# cpu2_lock_control1.net
KiCad netlist of a schematic drawn in Altium Designer
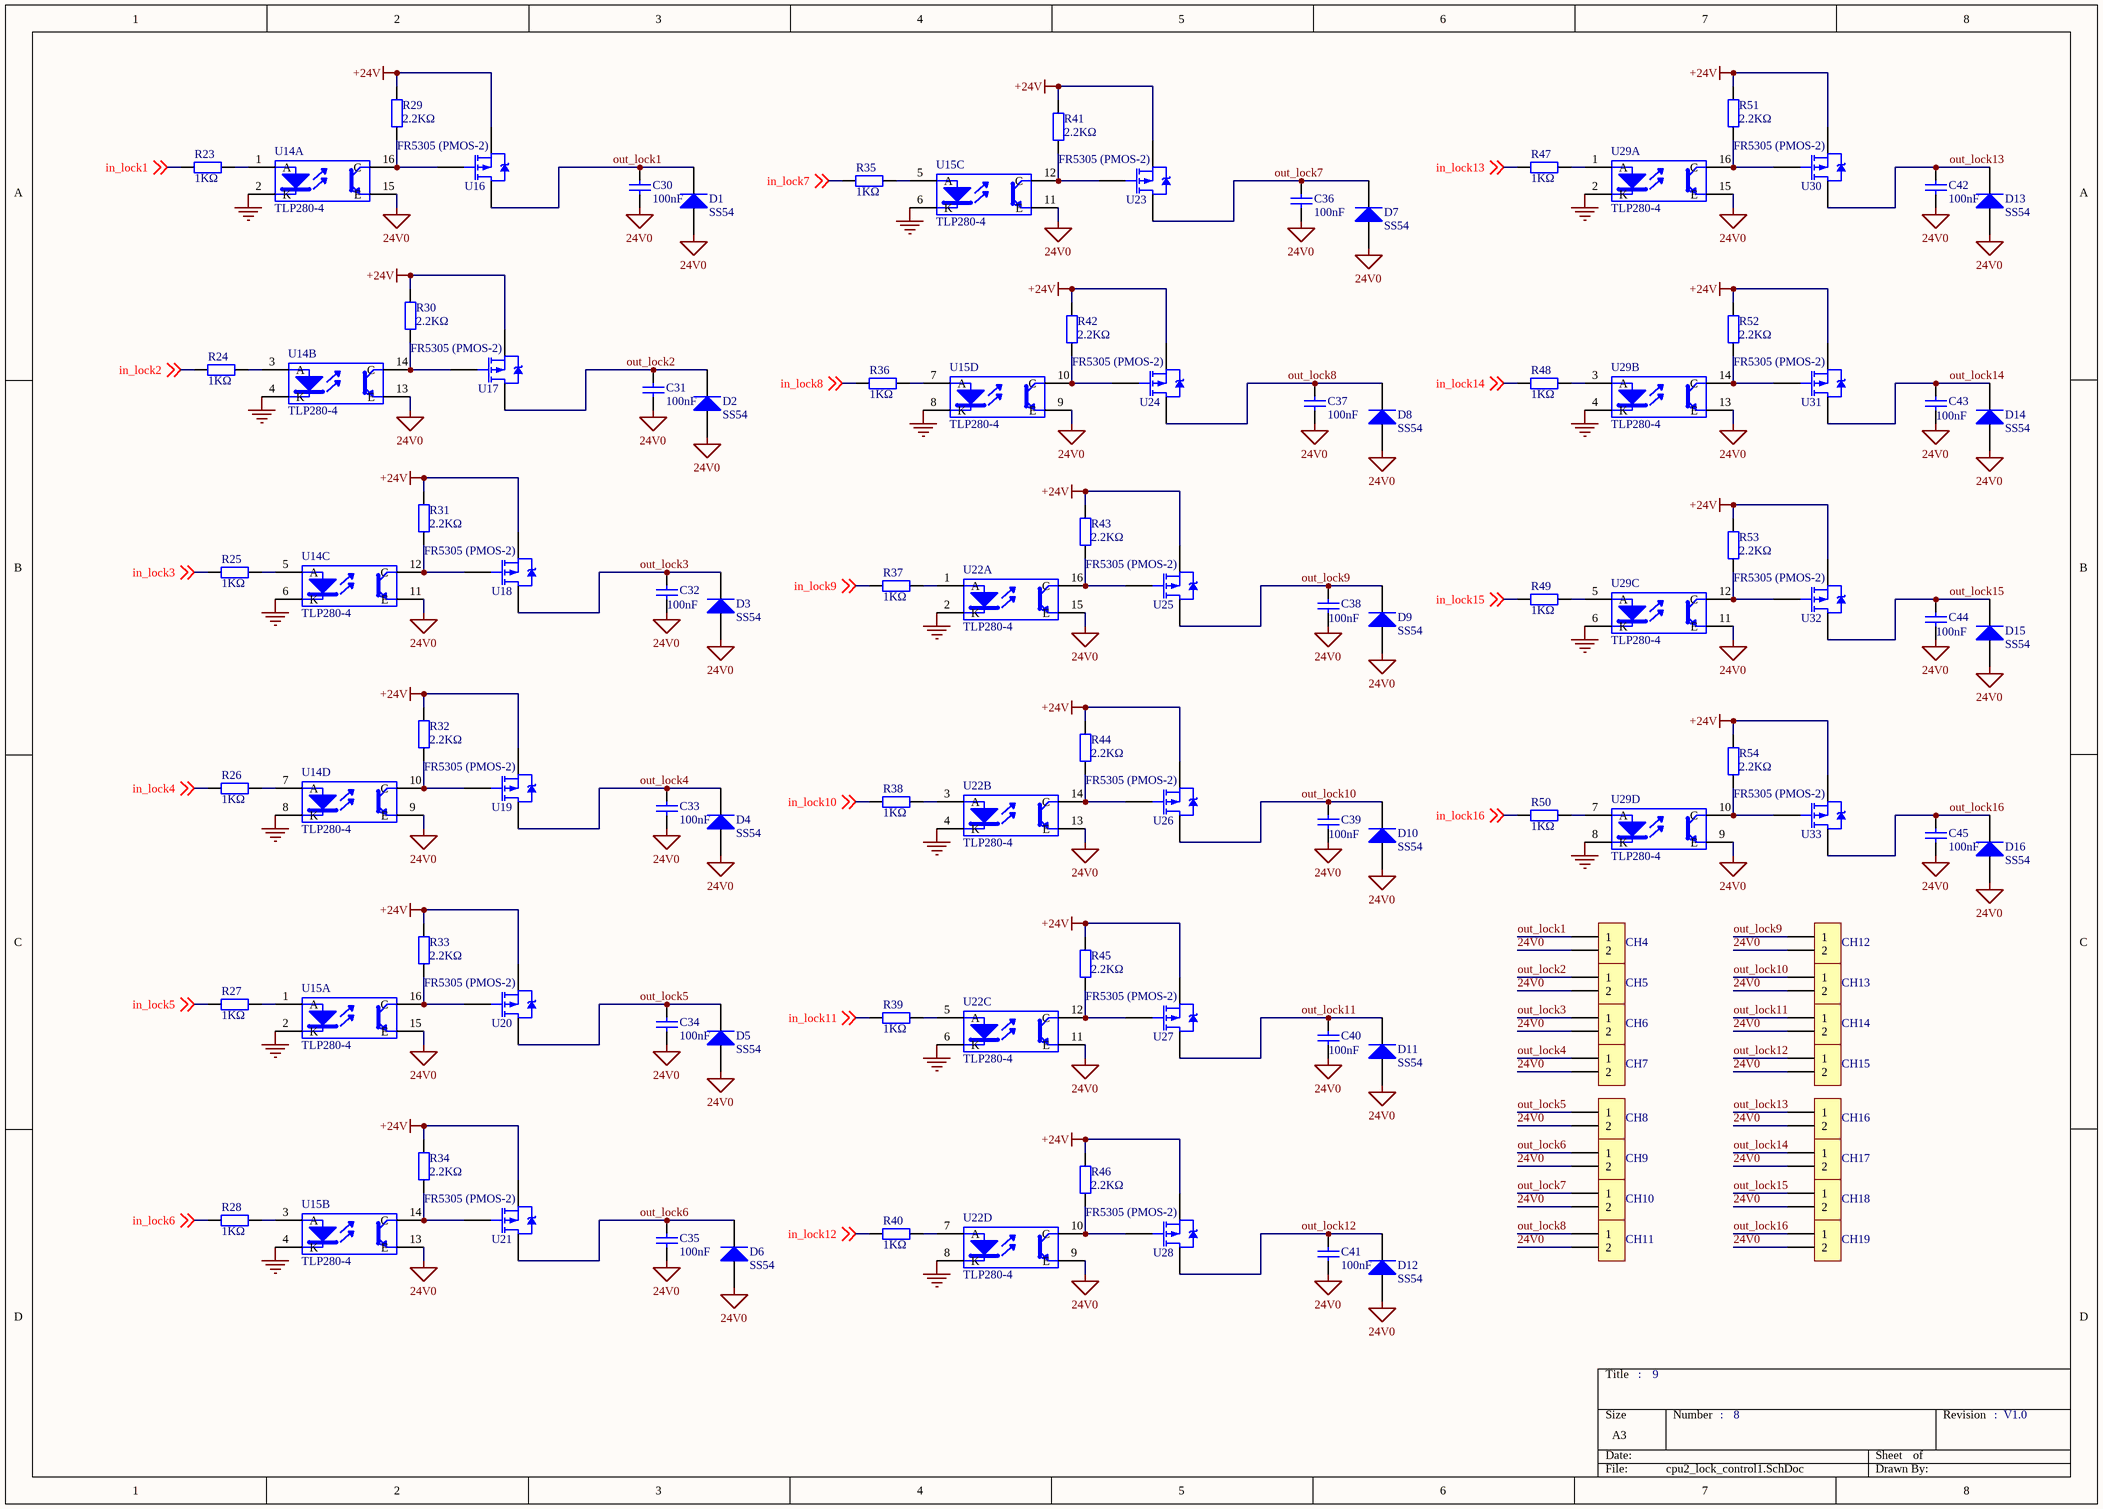
[diagram p0: cpu2_lock_control1.SchDoc]

(export (version "E")
  (design (tool "Eeschema 10.0.6"))
  (components
    (comp (ref "C30")
      (value "100nF")
      (footprint "0805_C")
      (description "贴片电容")
      (libsource (lib "Miscellaneous Devices LC") (part "0805 100nF(104) 10% 50V"))
    )
    (comp (ref "C31")
      (value "100nF")
      (footprint "0805_C")
      (description "贴片电容")
      (libsource (lib "Miscellaneous Devices LC") (part "0805 100nF(104) 10% 50V"))
    )
    (comp (ref "C32")
      (value "100nF")
      (footprint "0805_C")
      (description "贴片电容")
      (libsource (lib "Miscellaneous Devices LC") (part "0805 100nF(104) 10% 50V"))
    )
    (comp (ref "C33")
      (value "100nF")
      (footprint "0805_C")
      (description "贴片电容")
      (libsource (lib "Miscellaneous Devices LC") (part "0805 100nF(104) 10% 50V"))
    )
    (comp (ref "C34")
      (value "100nF")
      (footprint "0805_C")
      (description "贴片电容")
      (libsource (lib "Miscellaneous Devices LC") (part "0805 100nF(104) 10% 50V"))
    )
    (comp (ref "C35")
      (value "100nF")
      (footprint "0805_C")
      (description "贴片电容")
      (libsource (lib "Miscellaneous Devices LC") (part "0805 100nF(104) 10% 50V"))
    )
    (comp (ref "C36")
      (value "100nF")
      (footprint "0805_C")
      (description "贴片电容")
      (libsource (lib "Miscellaneous Devices LC") (part "0805 100nF(104) 10% 50V"))
    )
    (comp (ref "C37")
      (value "100nF")
      (footprint "0805_C")
      (description "贴片电容")
      (libsource (lib "Miscellaneous Devices LC") (part "0805 100nF(104) 10% 50V"))
    )
    (comp (ref "C38")
      (value "100nF")
      (footprint "0805_C")
      (description "贴片电容")
      (libsource (lib "Miscellaneous Devices LC") (part "0805 100nF(104) 10% 50V"))
    )
    (comp (ref "C39")
      (value "100nF")
      (footprint "0805_C")
      (description "贴片电容")
      (libsource (lib "Miscellaneous Devices LC") (part "0805 100nF(104) 10% 50V"))
    )
    (comp (ref "C40")
      (value "100nF")
      (footprint "0805_C")
      (description "贴片电容")
      (libsource (lib "Miscellaneous Devices LC") (part "0805 100nF(104) 10% 50V"))
    )
    (comp (ref "C41")
      (value "100nF")
      (footprint "0805_C")
      (description "贴片电容")
      (libsource (lib "Miscellaneous Devices LC") (part "0805 100nF(104) 10% 50V"))
    )
    (comp (ref "C42")
      (value "100nF")
      (footprint "0805_C")
      (description "贴片电容")
      (libsource (lib "Miscellaneous Devices LC") (part "0805 100nF(104) 10% 50V"))
    )
    (comp (ref "C43")
      (value "100nF")
      (footprint "0805_C")
      (description "贴片电容")
      (libsource (lib "Miscellaneous Devices LC") (part "0805 100nF(104) 10% 50V"))
    )
    (comp (ref "C44")
      (value "100nF")
      (footprint "0805_C")
      (description "贴片电容")
      (libsource (lib "Miscellaneous Devices LC") (part "0805 100nF(104) 10% 50V"))
    )
    (comp (ref "C45")
      (value "100nF")
      (footprint "0805_C")
      (description "贴片电容")
      (libsource (lib "Miscellaneous Devices LC") (part "0805 100nF(104) 10% 50V"))
    )
    (comp (ref "CH4")
      (value "HEADER1X2")
      (footprint "CH3.96-2PIN")
      (libsource (lib "myIntegrated_Library1") (part "HEADER1X2"))
    )
    (comp (ref "CH5")
      (value "HEADER1X2")
      (footprint "CH3.96-2PIN")
      (libsource (lib "myIntegrated_Library1") (part "HEADER1X2"))
    )
    (comp (ref "CH6")
      (value "HEADER1X2")
      (footprint "CH3.96-2PIN")
      (libsource (lib "myIntegrated_Library1") (part "HEADER1X2"))
    )
    (comp (ref "CH7")
      (value "HEADER1X2")
      (footprint "CH3.96-2PIN")
      (libsource (lib "myIntegrated_Library1") (part "HEADER1X2"))
    )
    (comp (ref "CH8")
      (value "HEADER1X2")
      (footprint "CH3.96-2PIN")
      (libsource (lib "myIntegrated_Library1") (part "HEADER1X2"))
    )
    (comp (ref "CH9")
      (value "HEADER1X2")
      (footprint "CH3.96-2PIN")
      (libsource (lib "myIntegrated_Library1") (part "HEADER1X2"))
    )
    (comp (ref "CH10")
      (value "HEADER1X2")
      (footprint "CH3.96-2PIN")
      (libsource (lib "myIntegrated_Library1") (part "HEADER1X2"))
    )
    (comp (ref "CH11")
      (value "HEADER1X2")
      (footprint "CH3.96-2PIN")
      (libsource (lib "myIntegrated_Library1") (part "HEADER1X2"))
    )
    (comp (ref "CH12")
      (value "HEADER1X2")
      (footprint "CH3.96-2PIN")
      (libsource (lib "myIntegrated_Library1") (part "HEADER1X2"))
    )
    (comp (ref "CH13")
      (value "HEADER1X2")
      (footprint "CH3.96-2PIN")
      (libsource (lib "myIntegrated_Library1") (part "HEADER1X2"))
    )
    (comp (ref "CH14")
      (value "HEADER1X2")
      (footprint "CH3.96-2PIN")
      (libsource (lib "myIntegrated_Library1") (part "HEADER1X2"))
    )
    (comp (ref "CH15")
      (value "HEADER1X2")
      (footprint "CH3.96-2PIN")
      (libsource (lib "myIntegrated_Library1") (part "HEADER1X2"))
    )
    (comp (ref "CH16")
      (value "HEADER1X2")
      (footprint "CH3.96-2PIN")
      (libsource (lib "myIntegrated_Library1") (part "HEADER1X2"))
    )
    (comp (ref "CH17")
      (value "HEADER1X2")
      (footprint "CH3.96-2PIN")
      (libsource (lib "myIntegrated_Library1") (part "HEADER1X2"))
    )
    (comp (ref "CH18")
      (value "HEADER1X2")
      (footprint "CH3.96-2PIN")
      (libsource (lib "myIntegrated_Library1") (part "HEADER1X2"))
    )
    (comp (ref "CH19")
      (value "HEADER1X2")
      (footprint "CH3.96-2PIN")
      (libsource (lib "myIntegrated_Library1") (part "HEADER1X2"))
    )
    (comp (ref "D1")
      (value "SS54")
      (footprint "SMA(DO-214AC)_S1")
      (description "二极管")
      (libsource (lib "Miscellaneous Devices LC") (part "SMA(DO-214AC) SS54"))
    )
    (comp (ref "D2")
      (value "SS54")
      (footprint "SMA(DO-214AC)_S1")
      (description "二极管")
      (libsource (lib "Miscellaneous Devices LC") (part "SMA(DO-214AC) SS54"))
    )
    (comp (ref "D3")
      (value "SS54")
      (footprint "SMA(DO-214AC)_S1")
      (description "二极管")
      (libsource (lib "Miscellaneous Devices LC") (part "SMA(DO-214AC) SS54"))
    )
    (comp (ref "D4")
      (value "SS54")
      (footprint "SMA(DO-214AC)_S1")
      (description "二极管")
      (libsource (lib "Miscellaneous Devices LC") (part "SMA(DO-214AC) SS54"))
    )
    (comp (ref "D5")
      (value "SS54")
      (footprint "SMA(DO-214AC)_S1")
      (description "二极管")
      (libsource (lib "Miscellaneous Devices LC") (part "SMA(DO-214AC) SS54"))
    )
    (comp (ref "D6")
      (value "SS54")
      (footprint "SMA(DO-214AC)_S1")
      (description "二极管")
      (libsource (lib "Miscellaneous Devices LC") (part "SMA(DO-214AC) SS54"))
    )
    (comp (ref "D7")
      (value "SS54")
      (footprint "SMA(DO-214AC)_S1")
      (description "二极管")
      (libsource (lib "Miscellaneous Devices LC") (part "SMA(DO-214AC) SS54"))
    )
    (comp (ref "D8")
      (value "SS54")
      (footprint "SMA(DO-214AC)_S1")
      (description "二极管")
      (libsource (lib "Miscellaneous Devices LC") (part "SMA(DO-214AC) SS54"))
    )
    (comp (ref "D9")
      (value "SS54")
      (footprint "SMA(DO-214AC)_S1")
      (description "二极管")
      (libsource (lib "Miscellaneous Devices LC") (part "SMA(DO-214AC) SS54"))
    )
    (comp (ref "D10")
      (value "SS54")
      (footprint "SMA(DO-214AC)_S1")
      (description "二极管")
      (libsource (lib "Miscellaneous Devices LC") (part "SMA(DO-214AC) SS54"))
    )
    (comp (ref "D11")
      (value "SS54")
      (footprint "SMA(DO-214AC)_S1")
      (description "二极管")
      (libsource (lib "Miscellaneous Devices LC") (part "SMA(DO-214AC) SS54"))
    )
    (comp (ref "D12")
      (value "SS54")
      (footprint "SMA(DO-214AC)_S1")
      (description "二极管")
      (libsource (lib "Miscellaneous Devices LC") (part "SMA(DO-214AC) SS54"))
    )
    (comp (ref "D13")
      (value "SS54")
      (footprint "SMA(DO-214AC)_S1")
      (description "二极管")
      (libsource (lib "Miscellaneous Devices LC") (part "SMA(DO-214AC) SS54"))
    )
    (comp (ref "D14")
      (value "SS54")
      (footprint "SMA(DO-214AC)_S1")
      (description "二极管")
      (libsource (lib "Miscellaneous Devices LC") (part "SMA(DO-214AC) SS54"))
    )
    (comp (ref "D15")
      (value "SS54")
      (footprint "SMA(DO-214AC)_S1")
      (description "二极管")
      (libsource (lib "Miscellaneous Devices LC") (part "SMA(DO-214AC) SS54"))
    )
    (comp (ref "D16")
      (value "SS54")
      (footprint "SMA(DO-214AC)_S1")
      (description "二极管")
      (libsource (lib "Miscellaneous Devices LC") (part "SMA(DO-214AC) SS54"))
    )
    (comp (ref "R23")
      (value "1KΩ")
      (footprint "0805_R")
      (description "贴片电阻")
      (libsource (lib "Miscellaneous Devices LC") (part "0805 11KΩ (1102) 1%"))
    )
    (comp (ref "R24")
      (value "1KΩ")
      (footprint "0805_R")
      (description "贴片电阻")
      (libsource (lib "Miscellaneous Devices LC") (part "0805 11KΩ (1102) 1%"))
    )
    (comp (ref "R25")
      (value "1KΩ")
      (footprint "0805_R")
      (description "贴片电阻")
      (libsource (lib "Miscellaneous Devices LC") (part "0805 11KΩ (1102) 1%"))
    )
    (comp (ref "R26")
      (value "1KΩ")
      (footprint "0805_R")
      (description "贴片电阻")
      (libsource (lib "Miscellaneous Devices LC") (part "0805 11KΩ (1102) 1%"))
    )
    (comp (ref "R27")
      (value "1KΩ")
      (footprint "0805_R")
      (description "贴片电阻")
      (libsource (lib "Miscellaneous Devices LC") (part "0805 11KΩ (1102) 1%"))
    )
    (comp (ref "R28")
      (value "1KΩ")
      (footprint "0805_R")
      (description "贴片电阻")
      (libsource (lib "Miscellaneous Devices LC") (part "0805 11KΩ (1102) 1%"))
    )
    (comp (ref "R29")
      (value "2.2KΩ")
      (footprint "0805_R")
      (description "贴片电阻")
      (libsource (lib "") (part "0805 11KΩ (1102) 1%_1"))
    )
    (comp (ref "R30")
      (value "2.2KΩ")
      (footprint "0805_R")
      (description "贴片电阻")
      (libsource (lib "") (part "0805 11KΩ (1102) 1%_1"))
    )
    (comp (ref "R31")
      (value "2.2KΩ")
      (footprint "0805_R")
      (description "贴片电阻")
      (libsource (lib "") (part "0805 11KΩ (1102) 1%_1"))
    )
    (comp (ref "R32")
      (value "2.2KΩ")
      (footprint "0805_R")
      (description "贴片电阻")
      (libsource (lib "") (part "0805 11KΩ (1102) 1%_1"))
    )
    (comp (ref "R33")
      (value "2.2KΩ")
      (footprint "0805_R")
      (description "贴片电阻")
      (libsource (lib "") (part "0805 11KΩ (1102) 1%_1"))
    )
    (comp (ref "R34")
      (value "2.2KΩ")
      (footprint "0805_R")
      (description "贴片电阻")
      (libsource (lib "") (part "0805 11KΩ (1102) 1%_1"))
    )
    (comp (ref "R35")
      (value "1KΩ")
      (footprint "0805_R")
      (description "贴片电阻")
      (libsource (lib "Miscellaneous Devices LC") (part "0805 11KΩ (1102) 1%"))
    )
    (comp (ref "R36")
      (value "1KΩ")
      (footprint "0805_R")
      (description "贴片电阻")
      (libsource (lib "Miscellaneous Devices LC") (part "0805 11KΩ (1102) 1%"))
    )
    (comp (ref "R37")
      (value "1KΩ")
      (footprint "0805_R")
      (description "贴片电阻")
      (libsource (lib "Miscellaneous Devices LC") (part "0805 11KΩ (1102) 1%"))
    )
    (comp (ref "R38")
      (value "1KΩ")
      (footprint "0805_R")
      (description "贴片电阻")
      (libsource (lib "Miscellaneous Devices LC") (part "0805 11KΩ (1102) 1%"))
    )
    (comp (ref "R39")
      (value "1KΩ")
      (footprint "0805_R")
      (description "贴片电阻")
      (libsource (lib "Miscellaneous Devices LC") (part "0805 11KΩ (1102) 1%"))
    )
    (comp (ref "R40")
      (value "1KΩ")
      (footprint "0805_R")
      (description "贴片电阻")
      (libsource (lib "Miscellaneous Devices LC") (part "0805 11KΩ (1102) 1%"))
    )
    (comp (ref "R41")
      (value "2.2KΩ")
      (footprint "0805_R")
      (description "贴片电阻")
      (libsource (lib "") (part "0805 11KΩ (1102) 1%_1"))
    )
    (comp (ref "R42")
      (value "2.2KΩ")
      (footprint "0805_R")
      (description "贴片电阻")
      (libsource (lib "") (part "0805 11KΩ (1102) 1%_1"))
    )
    (comp (ref "R43")
      (value "2.2KΩ")
      (footprint "0805_R")
      (description "贴片电阻")
      (libsource (lib "") (part "0805 11KΩ (1102) 1%_1"))
    )
    (comp (ref "R44")
      (value "2.2KΩ")
      (footprint "0805_R")
      (description "贴片电阻")
      (libsource (lib "") (part "0805 11KΩ (1102) 1%_1"))
    )
    (comp (ref "R45")
      (value "2.2KΩ")
      (footprint "0805_R")
      (description "贴片电阻")
      (libsource (lib "") (part "0805 11KΩ (1102) 1%_1"))
    )
    (comp (ref "R46")
      (value "2.2KΩ")
      (footprint "0805_R")
      (description "贴片电阻")
      (libsource (lib "") (part "0805 11KΩ (1102) 1%_1"))
    )
    (comp (ref "R47")
      (value "1KΩ")
      (footprint "0805_R")
      (description "贴片电阻")
      (libsource (lib "Miscellaneous Devices LC") (part "0805 11KΩ (1102) 1%"))
    )
    (comp (ref "R48")
      (value "1KΩ")
      (footprint "0805_R")
      (description "贴片电阻")
      (libsource (lib "Miscellaneous Devices LC") (part "0805 11KΩ (1102) 1%"))
    )
    (comp (ref "R49")
      (value "1KΩ")
      (footprint "0805_R")
      (description "贴片电阻")
      (libsource (lib "Miscellaneous Devices LC") (part "0805 11KΩ (1102) 1%"))
    )
    (comp (ref "R50")
      (value "1KΩ")
      (footprint "0805_R")
      (description "贴片电阻")
      (libsource (lib "Miscellaneous Devices LC") (part "0805 11KΩ (1102) 1%"))
    )
    (comp (ref "R51")
      (value "2.2KΩ")
      (footprint "0805_R")
      (description "贴片电阻")
      (libsource (lib "") (part "0805 11KΩ (1102) 1%_1"))
    )
    (comp (ref "R52")
      (value "2.2KΩ")
      (footprint "0805_R")
      (description "贴片电阻")
      (libsource (lib "") (part "0805 11KΩ (1102) 1%_1"))
    )
    (comp (ref "R53")
      (value "2.2KΩ")
      (footprint "0805_R")
      (description "贴片电阻")
      (libsource (lib "") (part "0805 11KΩ (1102) 1%_1"))
    )
    (comp (ref "R54")
      (value "2.2KΩ")
      (footprint "0805_R")
      (description "贴片电阻")
      (libsource (lib "") (part "0805 11KΩ (1102) 1%_1"))
    )
    (comp (ref "U14") (value "TLP280-4") (footprint "SO16") (libsource (lib "WH V20") (part "TLP521-4")))
    (comp (ref "U15") (value "TLP280-4") (footprint "SO16") (libsource (lib "WH V20") (part "TLP521-4")))
    (comp (ref "U16")
      (value "FR5305 (PMOS-2)")
      (footprint "TO-252")
      (description "P-Channel Power MOSFET")
      (fields (field (name "PUBLISHER") "Altium Limited"))
      (libsource (lib "Miscellaneous Devices") (part "PMOS-2"))
    )
    (comp (ref "U17")
      (value "FR5305 (PMOS-2)")
      (footprint "TO-252")
      (description "P-Channel Power MOSFET")
      (fields (field (name "PUBLISHER") "Altium Limited"))
      (libsource (lib "Miscellaneous Devices") (part "PMOS-2"))
    )
    (comp (ref "U18")
      (value "FR5305 (PMOS-2)")
      (footprint "TO-252")
      (description "P-Channel Power MOSFET")
      (fields (field (name "PUBLISHER") "Altium Limited"))
      (libsource (lib "Miscellaneous Devices") (part "PMOS-2"))
    )
    (comp (ref "U19")
      (value "FR5305 (PMOS-2)")
      (footprint "TO-252")
      (description "P-Channel Power MOSFET")
      (fields (field (name "PUBLISHER") "Altium Limited"))
      (libsource (lib "Miscellaneous Devices") (part "PMOS-2"))
    )
    (comp (ref "U20")
      (value "FR5305 (PMOS-2)")
      (footprint "TO-252")
      (description "P-Channel Power MOSFET")
      (fields (field (name "PUBLISHER") "Altium Limited"))
      (libsource (lib "Miscellaneous Devices") (part "PMOS-2"))
    )
    (comp (ref "U21")
      (value "FR5305 (PMOS-2)")
      (footprint "TO-252")
      (description "P-Channel Power MOSFET")
      (fields (field (name "PUBLISHER") "Altium Limited"))
      (libsource (lib "Miscellaneous Devices") (part "PMOS-2"))
    )
    (comp (ref "U22") (value "TLP280-4") (footprint "SO16") (libsource (lib "WH V20") (part "TLP521-4")))
    (comp (ref "U23")
      (value "FR5305 (PMOS-2)")
      (footprint "TO-252")
      (description "P-Channel Power MOSFET")
      (fields (field (name "PUBLISHER") "Altium Limited"))
      (libsource (lib "Miscellaneous Devices") (part "PMOS-2"))
    )
    (comp (ref "U24")
      (value "FR5305 (PMOS-2)")
      (footprint "TO-252")
      (description "P-Channel Power MOSFET")
      (fields (field (name "PUBLISHER") "Altium Limited"))
      (libsource (lib "Miscellaneous Devices") (part "PMOS-2"))
    )
    (comp (ref "U25")
      (value "FR5305 (PMOS-2)")
      (footprint "TO-252")
      (description "P-Channel Power MOSFET")
      (fields (field (name "PUBLISHER") "Altium Limited"))
      (libsource (lib "Miscellaneous Devices") (part "PMOS-2"))
    )
    (comp (ref "U26")
      (value "FR5305 (PMOS-2)")
      (footprint "TO-252")
      (description "P-Channel Power MOSFET")
      (fields (field (name "PUBLISHER") "Altium Limited"))
      (libsource (lib "Miscellaneous Devices") (part "PMOS-2"))
    )
    (comp (ref "U27")
      (value "FR5305 (PMOS-2)")
      (footprint "TO-252")
      (description "P-Channel Power MOSFET")
      (fields (field (name "PUBLISHER") "Altium Limited"))
      (libsource (lib "Miscellaneous Devices") (part "PMOS-2"))
    )
    (comp (ref "U28")
      (value "FR5305 (PMOS-2)")
      (footprint "TO-252")
      (description "P-Channel Power MOSFET")
      (fields (field (name "PUBLISHER") "Altium Limited"))
      (libsource (lib "Miscellaneous Devices") (part "PMOS-2"))
    )
    (comp (ref "U29") (value "TLP280-4") (footprint "SO16") (libsource (lib "WH V20") (part "TLP521-4")))
    (comp (ref "U30")
      (value "FR5305 (PMOS-2)")
      (footprint "TO-252")
      (description "P-Channel Power MOSFET")
      (fields (field (name "PUBLISHER") "Altium Limited"))
      (libsource (lib "Miscellaneous Devices") (part "PMOS-2"))
    )
    (comp (ref "U31")
      (value "FR5305 (PMOS-2)")
      (footprint "TO-252")
      (description "P-Channel Power MOSFET")
      (fields (field (name "PUBLISHER") "Altium Limited"))
      (libsource (lib "Miscellaneous Devices") (part "PMOS-2"))
    )
    (comp (ref "U32")
      (value "FR5305 (PMOS-2)")
      (footprint "TO-252")
      (description "P-Channel Power MOSFET")
      (fields (field (name "PUBLISHER") "Altium Limited"))
      (libsource (lib "Miscellaneous Devices") (part "PMOS-2"))
    )
    (comp (ref "U33")
      (value "FR5305 (PMOS-2)")
      (footprint "TO-252")
      (description "P-Channel Power MOSFET")
      (fields (field (name "PUBLISHER") "Altium Limited"))
      (libsource (lib "Miscellaneous Devices") (part "PMOS-2"))
    )
  )
  (nets
    (net (code "1") (name "+24V") (class "Default")
      (node (ref "R29") (pin "2") (pinfunction "2_2") (pintype "passive"))
      (node (ref "R30") (pin "2") (pinfunction "2_2") (pintype "passive"))
      (node (ref "R31") (pin "2") (pinfunction "2_2") (pintype "passive"))
      (node (ref "R32") (pin "2") (pinfunction "2_2") (pintype "passive"))
      (node (ref "R33") (pin "2") (pinfunction "2_2") (pintype "passive"))
      (node (ref "R34") (pin "2") (pinfunction "2_2") (pintype "passive"))
      (node (ref "R41") (pin "2") (pinfunction "2_2") (pintype "passive"))
      (node (ref "R42") (pin "2") (pinfunction "2_2") (pintype "passive"))
      (node (ref "R43") (pin "2") (pinfunction "2_2") (pintype "passive"))
      (node (ref "R44") (pin "2") (pinfunction "2_2") (pintype "passive"))
      (node (ref "R45") (pin "2") (pinfunction "2_2") (pintype "passive"))
      (node (ref "R46") (pin "2") (pinfunction "2_2") (pintype "passive"))
      (node (ref "R51") (pin "2") (pinfunction "2_2") (pintype "passive"))
      (node (ref "R52") (pin "2") (pinfunction "2_2") (pintype "passive"))
      (node (ref "R53") (pin "2") (pinfunction "2_2") (pintype "passive"))
      (node (ref "R54") (pin "2") (pinfunction "2_2") (pintype "passive"))
      (node (ref "U16") (pin "3") (pinfunction "S_3") (pintype "passive"))
      (node (ref "U17") (pin "3") (pinfunction "S_3") (pintype "passive"))
      (node (ref "U18") (pin "3") (pinfunction "S_3") (pintype "passive"))
      (node (ref "U19") (pin "3") (pinfunction "S_3") (pintype "passive"))
      (node (ref "U20") (pin "3") (pinfunction "S_3") (pintype "passive"))
      (node (ref "U21") (pin "3") (pinfunction "S_3") (pintype "passive"))
      (node (ref "U23") (pin "3") (pinfunction "S_3") (pintype "passive"))
      (node (ref "U24") (pin "3") (pinfunction "S_3") (pintype "passive"))
      (node (ref "U25") (pin "3") (pinfunction "S_3") (pintype "passive"))
      (node (ref "U26") (pin "3") (pinfunction "S_3") (pintype "passive"))
      (node (ref "U27") (pin "3") (pinfunction "S_3") (pintype "passive"))
      (node (ref "U28") (pin "3") (pinfunction "S_3") (pintype "passive"))
      (node (ref "U30") (pin "3") (pinfunction "S_3") (pintype "passive"))
      (node (ref "U31") (pin "3") (pinfunction "S_3") (pintype "passive"))
      (node (ref "U32") (pin "3") (pinfunction "S_3") (pintype "passive"))
      (node (ref "U33") (pin "3") (pinfunction "S_3") (pintype "passive"))
    )
    (net (code "2") (name "/out_lock1") (class "Default")
      (node (ref "C30") (pin "2") (pinfunction "2_2") (pintype "passive"))
      (node (ref "CH4") (pin "1") (pinfunction "1_1") (pintype "passive"))
      (node (ref "D1") (pin "2") (pinfunction "K_2") (pintype "passive"))
      (node (ref "U16") (pin "2") (pinfunction "D_2") (pintype "passive"))
    )
    (net (code "3") (name "/out_lock2") (class "Default")
      (node (ref "C31") (pin "2") (pinfunction "2_2") (pintype "passive"))
      (node (ref "CH5") (pin "1") (pinfunction "1_1") (pintype "passive"))
      (node (ref "D2") (pin "2") (pinfunction "K_2") (pintype "passive"))
      (node (ref "U17") (pin "2") (pinfunction "D_2") (pintype "passive"))
    )
    (net (code "4") (name "/out_lock3") (class "Default")
      (node (ref "C32") (pin "2") (pinfunction "2_2") (pintype "passive"))
      (node (ref "CH6") (pin "1") (pinfunction "1_1") (pintype "passive"))
      (node (ref "D3") (pin "2") (pinfunction "K_2") (pintype "passive"))
      (node (ref "U18") (pin "2") (pinfunction "D_2") (pintype "passive"))
    )
    (net (code "5") (name "/out_lock4") (class "Default")
      (node (ref "C33") (pin "2") (pinfunction "2_2") (pintype "passive"))
      (node (ref "CH7") (pin "1") (pinfunction "1_1") (pintype "passive"))
      (node (ref "D4") (pin "2") (pinfunction "K_2") (pintype "passive"))
      (node (ref "U19") (pin "2") (pinfunction "D_2") (pintype "passive"))
    )
    (net (code "6") (name "/out_lock5") (class "Default")
      (node (ref "C34") (pin "2") (pinfunction "2_2") (pintype "passive"))
      (node (ref "CH8") (pin "1") (pinfunction "1_1") (pintype "passive"))
      (node (ref "D5") (pin "2") (pinfunction "K_2") (pintype "passive"))
      (node (ref "U20") (pin "2") (pinfunction "D_2") (pintype "passive"))
    )
    (net (code "7") (name "/out_lock6") (class "Default")
      (node (ref "C35") (pin "2") (pinfunction "2_2") (pintype "passive"))
      (node (ref "CH9") (pin "1") (pinfunction "1_1") (pintype "passive"))
      (node (ref "D6") (pin "2") (pinfunction "K_2") (pintype "passive"))
      (node (ref "U21") (pin "2") (pinfunction "D_2") (pintype "passive"))
    )
    (net (code "8") (name "/out_lock7") (class "Default")
      (node (ref "C36") (pin "2") (pinfunction "2_2") (pintype "passive"))
      (node (ref "CH10") (pin "1") (pinfunction "1_1") (pintype "passive"))
      (node (ref "D7") (pin "2") (pinfunction "K_2") (pintype "passive"))
      (node (ref "U23") (pin "2") (pinfunction "D_2") (pintype "passive"))
    )
    (net (code "9") (name "/out_lock8") (class "Default")
      (node (ref "C37") (pin "2") (pinfunction "2_2") (pintype "passive"))
      (node (ref "CH11") (pin "1") (pinfunction "1_1") (pintype "passive"))
      (node (ref "D8") (pin "2") (pinfunction "K_2") (pintype "passive"))
      (node (ref "U24") (pin "2") (pinfunction "D_2") (pintype "passive"))
    )
    (net (code "10") (name "/out_lock9") (class "Default")
      (node (ref "C38") (pin "2") (pinfunction "2_2") (pintype "passive"))
      (node (ref "CH12") (pin "1") (pinfunction "1_1") (pintype "passive"))
      (node (ref "D9") (pin "2") (pinfunction "K_2") (pintype "passive"))
      (node (ref "U25") (pin "2") (pinfunction "D_2") (pintype "passive"))
    )
    (net (code "11") (name "/out_lock10") (class "Default")
      (node (ref "C39") (pin "2") (pinfunction "2_2") (pintype "passive"))
      (node (ref "CH13") (pin "1") (pinfunction "1_1") (pintype "passive"))
      (node (ref "D10") (pin "2") (pinfunction "K_2") (pintype "passive"))
      (node (ref "U26") (pin "2") (pinfunction "D_2") (pintype "passive"))
    )
    (net (code "12") (name "/out_lock11") (class "Default")
      (node (ref "C40") (pin "2") (pinfunction "2_2") (pintype "passive"))
      (node (ref "CH14") (pin "1") (pinfunction "1_1") (pintype "passive"))
      (node (ref "D11") (pin "2") (pinfunction "K_2") (pintype "passive"))
      (node (ref "U27") (pin "2") (pinfunction "D_2") (pintype "passive"))
    )
    (net (code "13") (name "/out_lock12") (class "Default")
      (node (ref "C41") (pin "2") (pinfunction "2_2") (pintype "passive"))
      (node (ref "CH15") (pin "1") (pinfunction "1_1") (pintype "passive"))
      (node (ref "D12") (pin "2") (pinfunction "K_2") (pintype "passive"))
      (node (ref "U28") (pin "2") (pinfunction "D_2") (pintype "passive"))
    )
    (net (code "14") (name "/out_lock13") (class "Default")
      (node (ref "C42") (pin "2") (pinfunction "2_2") (pintype "passive"))
      (node (ref "CH16") (pin "1") (pinfunction "1_1") (pintype "passive"))
      (node (ref "D13") (pin "2") (pinfunction "K_2") (pintype "passive"))
      (node (ref "U30") (pin "2") (pinfunction "D_2") (pintype "passive"))
    )
    (net (code "15") (name "/out_lock14") (class "Default")
      (node (ref "C43") (pin "2") (pinfunction "2_2") (pintype "passive"))
      (node (ref "CH17") (pin "1") (pinfunction "1_1") (pintype "passive"))
      (node (ref "D14") (pin "2") (pinfunction "K_2") (pintype "passive"))
      (node (ref "U31") (pin "2") (pinfunction "D_2") (pintype "passive"))
    )
    (net (code "16") (name "/out_lock15") (class "Default")
      (node (ref "C44") (pin "2") (pinfunction "2_2") (pintype "passive"))
      (node (ref "CH18") (pin "1") (pinfunction "1_1") (pintype "passive"))
      (node (ref "D15") (pin "2") (pinfunction "K_2") (pintype "passive"))
      (node (ref "U32") (pin "2") (pinfunction "D_2") (pintype "passive"))
    )
    (net (code "17") (name "/out_lock16") (class "Default")
      (node (ref "C45") (pin "2") (pinfunction "2_2") (pintype "passive"))
      (node (ref "CH19") (pin "1") (pinfunction "1_1") (pintype "passive"))
      (node (ref "D16") (pin "2") (pinfunction "K_2") (pintype "passive"))
      (node (ref "U33") (pin "2") (pinfunction "D_2") (pintype "passive"))
    )
    (net (code "18") (name "24V0") (class "Default")
      (node (ref "C30") (pin "1") (pinfunction "1_1") (pintype "passive"))
      (node (ref "C31") (pin "1") (pinfunction "1_1") (pintype "passive"))
      (node (ref "C32") (pin "1") (pinfunction "1_1") (pintype "passive"))
      (node (ref "C33") (pin "1") (pinfunction "1_1") (pintype "passive"))
      (node (ref "C34") (pin "1") (pinfunction "1_1") (pintype "passive"))
      (node (ref "C35") (pin "1") (pinfunction "1_1") (pintype "passive"))
      (node (ref "C36") (pin "1") (pinfunction "1_1") (pintype "passive"))
      (node (ref "C37") (pin "1") (pinfunction "1_1") (pintype "passive"))
      (node (ref "C38") (pin "1") (pinfunction "1_1") (pintype "passive"))
      (node (ref "C39") (pin "1") (pinfunction "1_1") (pintype "passive"))
      (node (ref "C40") (pin "1") (pinfunction "1_1") (pintype "passive"))
      (node (ref "C41") (pin "1") (pinfunction "1_1") (pintype "passive"))
      (node (ref "C42") (pin "1") (pinfunction "1_1") (pintype "passive"))
      (node (ref "C43") (pin "1") (pinfunction "1_1") (pintype "passive"))
      (node (ref "C44") (pin "1") (pinfunction "1_1") (pintype "passive"))
      (node (ref "C45") (pin "1") (pinfunction "1_1") (pintype "passive"))
      (node (ref "CH10") (pin "2") (pinfunction "2_2") (pintype "passive"))
      (node (ref "CH11") (pin "2") (pinfunction "2_2") (pintype "passive"))
      (node (ref "CH12") (pin "2") (pinfunction "2_2") (pintype "passive"))
      (node (ref "CH13") (pin "2") (pinfunction "2_2") (pintype "passive"))
      (node (ref "CH14") (pin "2") (pinfunction "2_2") (pintype "passive"))
      (node (ref "CH15") (pin "2") (pinfunction "2_2") (pintype "passive"))
      (node (ref "CH16") (pin "2") (pinfunction "2_2") (pintype "passive"))
      (node (ref "CH17") (pin "2") (pinfunction "2_2") (pintype "passive"))
      (node (ref "CH18") (pin "2") (pinfunction "2_2") (pintype "passive"))
      (node (ref "CH19") (pin "2") (pinfunction "2_2") (pintype "passive"))
      (node (ref "CH4") (pin "2") (pinfunction "2_2") (pintype "passive"))
      (node (ref "CH5") (pin "2") (pinfunction "2_2") (pintype "passive"))
      (node (ref "CH6") (pin "2") (pinfunction "2_2") (pintype "passive"))
      (node (ref "CH7") (pin "2") (pinfunction "2_2") (pintype "passive"))
      (node (ref "CH8") (pin "2") (pinfunction "2_2") (pintype "passive"))
      (node (ref "CH9") (pin "2") (pinfunction "2_2") (pintype "passive"))
      (node (ref "D1") (pin "1") (pinfunction "A_1") (pintype "passive"))
      (node (ref "D10") (pin "1") (pinfunction "A_1") (pintype "passive"))
      (node (ref "D11") (pin "1") (pinfunction "A_1") (pintype "passive"))
      (node (ref "D12") (pin "1") (pinfunction "A_1") (pintype "passive"))
      (node (ref "D13") (pin "1") (pinfunction "A_1") (pintype "passive"))
      (node (ref "D14") (pin "1") (pinfunction "A_1") (pintype "passive"))
      (node (ref "D15") (pin "1") (pinfunction "A_1") (pintype "passive"))
      (node (ref "D16") (pin "1") (pinfunction "A_1") (pintype "passive"))
      (node (ref "D2") (pin "1") (pinfunction "A_1") (pintype "passive"))
      (node (ref "D3") (pin "1") (pinfunction "A_1") (pintype "passive"))
      (node (ref "D4") (pin "1") (pinfunction "A_1") (pintype "passive"))
      (node (ref "D5") (pin "1") (pinfunction "A_1") (pintype "passive"))
      (node (ref "D6") (pin "1") (pinfunction "A_1") (pintype "passive"))
      (node (ref "D7") (pin "1") (pinfunction "A_1") (pintype "passive"))
      (node (ref "D8") (pin "1") (pinfunction "A_1") (pintype "passive"))
      (node (ref "D9") (pin "1") (pinfunction "A_1") (pintype "passive"))
      (node (ref "U14") (pin "11") (pinfunction "E_11") (pintype "passive"))
      (node (ref "U14") (pin "13") (pinfunction "E_13") (pintype "passive"))
      (node (ref "U14") (pin "15") (pinfunction "E_15") (pintype "passive"))
      (node (ref "U14") (pin "9") (pinfunction "E_9") (pintype "passive"))
      (node (ref "U15") (pin "11") (pinfunction "E_11") (pintype "passive"))
      (node (ref "U15") (pin "13") (pinfunction "E_13") (pintype "passive"))
      (node (ref "U15") (pin "15") (pinfunction "E_15") (pintype "passive"))
      (node (ref "U15") (pin "9") (pinfunction "E_9") (pintype "passive"))
      (node (ref "U22") (pin "11") (pinfunction "E_11") (pintype "passive"))
      (node (ref "U22") (pin "13") (pinfunction "E_13") (pintype "passive"))
      (node (ref "U22") (pin "15") (pinfunction "E_15") (pintype "passive"))
      (node (ref "U22") (pin "9") (pinfunction "E_9") (pintype "passive"))
      (node (ref "U29") (pin "11") (pinfunction "E_11") (pintype "passive"))
      (node (ref "U29") (pin "13") (pinfunction "E_13") (pintype "passive"))
      (node (ref "U29") (pin "15") (pinfunction "E_15") (pintype "passive"))
      (node (ref "U29") (pin "9") (pinfunction "E_9") (pintype "passive"))
    )
    (net (code "19") (name "GND") (class "Default")
      (node (ref "U14") (pin "2") (pinfunction "K_2") (pintype "passive"))
      (node (ref "U14") (pin "4") (pinfunction "K_4") (pintype "passive"))
      (node (ref "U14") (pin "6") (pinfunction "K_6") (pintype "passive"))
      (node (ref "U14") (pin "8") (pinfunction "K_8") (pintype "passive"))
      (node (ref "U15") (pin "2") (pinfunction "K_2") (pintype "passive"))
      (node (ref "U15") (pin "4") (pinfunction "K_4") (pintype "passive"))
      (node (ref "U15") (pin "6") (pinfunction "K_6") (pintype "passive"))
      (node (ref "U15") (pin "8") (pinfunction "K_8") (pintype "passive"))
      (node (ref "U22") (pin "2") (pinfunction "K_2") (pintype "passive"))
      (node (ref "U22") (pin "4") (pinfunction "K_4") (pintype "passive"))
      (node (ref "U22") (pin "6") (pinfunction "K_6") (pintype "passive"))
      (node (ref "U22") (pin "8") (pinfunction "K_8") (pintype "passive"))
      (node (ref "U29") (pin "2") (pinfunction "K_2") (pintype "passive"))
      (node (ref "U29") (pin "4") (pinfunction "K_4") (pintype "passive"))
      (node (ref "U29") (pin "6") (pinfunction "K_6") (pintype "passive"))
      (node (ref "U29") (pin "8") (pinfunction "K_8") (pintype "passive"))
    )
    (net (code "20") (name "Net-(U14A-A)") (class "Default")
      (node (ref "R23") (pin "2") (pinfunction "2_2") (pintype "passive"))
      (node (ref "U14") (pin "1") (pinfunction "A_1") (pintype "passive"))
    )
    (net (code "21") (name "Net-(U14A-C)") (class "Default")
      (node (ref "R29") (pin "1") (pinfunction "1_1") (pintype "passive"))
      (node (ref "U14") (pin "16") (pinfunction "C_16") (pintype "passive"))
      (node (ref "U16") (pin "1") (pinfunction "G_1") (pintype "passive"))
    )
    (net (code "22") (name "Net-(U14B-A)") (class "Default")
      (node (ref "R24") (pin "2") (pinfunction "2_2") (pintype "passive"))
      (node (ref "U14") (pin "3") (pinfunction "A_3") (pintype "passive"))
    )
    (net (code "23") (name "Net-(U14B-C)") (class "Default")
      (node (ref "R30") (pin "1") (pinfunction "1_1") (pintype "passive"))
      (node (ref "U14") (pin "14") (pinfunction "C_14") (pintype "passive"))
      (node (ref "U17") (pin "1") (pinfunction "G_1") (pintype "passive"))
    )
    (net (code "24") (name "Net-(U14C-A)") (class "Default")
      (node (ref "R25") (pin "2") (pinfunction "2_2") (pintype "passive"))
      (node (ref "U14") (pin "5") (pinfunction "A_5") (pintype "passive"))
    )
    (net (code "25") (name "Net-(U14C-C)") (class "Default")
      (node (ref "R31") (pin "1") (pinfunction "1_1") (pintype "passive"))
      (node (ref "U14") (pin "12") (pinfunction "C_12") (pintype "passive"))
      (node (ref "U18") (pin "1") (pinfunction "G_1") (pintype "passive"))
    )
    (net (code "26") (name "Net-(U14D-A)") (class "Default")
      (node (ref "R26") (pin "2") (pinfunction "2_2") (pintype "passive"))
      (node (ref "U14") (pin "7") (pinfunction "A_7") (pintype "passive"))
    )
    (net (code "27") (name "Net-(U14D-C)") (class "Default")
      (node (ref "R32") (pin "1") (pinfunction "1_1") (pintype "passive"))
      (node (ref "U14") (pin "10") (pinfunction "C_10") (pintype "passive"))
      (node (ref "U19") (pin "1") (pinfunction "G_1") (pintype "passive"))
    )
    (net (code "28") (name "Net-(U15A-A)") (class "Default")
      (node (ref "R27") (pin "2") (pinfunction "2_2") (pintype "passive"))
      (node (ref "U15") (pin "1") (pinfunction "A_1") (pintype "passive"))
    )
    (net (code "29") (name "Net-(U15A-C)") (class "Default")
      (node (ref "R33") (pin "1") (pinfunction "1_1") (pintype "passive"))
      (node (ref "U15") (pin "16") (pinfunction "C_16") (pintype "passive"))
      (node (ref "U20") (pin "1") (pinfunction "G_1") (pintype "passive"))
    )
    (net (code "30") (name "Net-(U15B-A)") (class "Default")
      (node (ref "R28") (pin "2") (pinfunction "2_2") (pintype "passive"))
      (node (ref "U15") (pin "3") (pinfunction "A_3") (pintype "passive"))
    )
    (net (code "31") (name "Net-(U15B-C)") (class "Default")
      (node (ref "R34") (pin "1") (pinfunction "1_1") (pintype "passive"))
      (node (ref "U15") (pin "14") (pinfunction "C_14") (pintype "passive"))
      (node (ref "U21") (pin "1") (pinfunction "G_1") (pintype "passive"))
    )
    (net (code "32") (name "Net-(U15C-A)") (class "Default")
      (node (ref "R35") (pin "2") (pinfunction "2_2") (pintype "passive"))
      (node (ref "U15") (pin "5") (pinfunction "A_5") (pintype "passive"))
    )
    (net (code "33") (name "Net-(U15C-C)") (class "Default")
      (node (ref "R41") (pin "1") (pinfunction "1_1") (pintype "passive"))
      (node (ref "U15") (pin "12") (pinfunction "C_12") (pintype "passive"))
      (node (ref "U23") (pin "1") (pinfunction "G_1") (pintype "passive"))
    )
    (net (code "34") (name "Net-(U15D-A)") (class "Default")
      (node (ref "R36") (pin "2") (pinfunction "2_2") (pintype "passive"))
      (node (ref "U15") (pin "7") (pinfunction "A_7") (pintype "passive"))
    )
    (net (code "35") (name "Net-(U15D-C)") (class "Default")
      (node (ref "R42") (pin "1") (pinfunction "1_1") (pintype "passive"))
      (node (ref "U15") (pin "10") (pinfunction "C_10") (pintype "passive"))
      (node (ref "U24") (pin "1") (pinfunction "G_1") (pintype "passive"))
    )
    (net (code "36") (name "Net-(U22A-A)") (class "Default")
      (node (ref "R37") (pin "2") (pinfunction "2_2") (pintype "passive"))
      (node (ref "U22") (pin "1") (pinfunction "A_1") (pintype "passive"))
    )
    (net (code "37") (name "Net-(U22A-C)") (class "Default")
      (node (ref "R43") (pin "1") (pinfunction "1_1") (pintype "passive"))
      (node (ref "U22") (pin "16") (pinfunction "C_16") (pintype "passive"))
      (node (ref "U25") (pin "1") (pinfunction "G_1") (pintype "passive"))
    )
    (net (code "38") (name "Net-(U22B-A)") (class "Default")
      (node (ref "R38") (pin "2") (pinfunction "2_2") (pintype "passive"))
      (node (ref "U22") (pin "3") (pinfunction "A_3") (pintype "passive"))
    )
    (net (code "39") (name "Net-(U22B-C)") (class "Default")
      (node (ref "R44") (pin "1") (pinfunction "1_1") (pintype "passive"))
      (node (ref "U22") (pin "14") (pinfunction "C_14") (pintype "passive"))
      (node (ref "U26") (pin "1") (pinfunction "G_1") (pintype "passive"))
    )
    (net (code "40") (name "Net-(U22C-A)") (class "Default")
      (node (ref "R39") (pin "2") (pinfunction "2_2") (pintype "passive"))
      (node (ref "U22") (pin "5") (pinfunction "A_5") (pintype "passive"))
    )
    (net (code "41") (name "Net-(U22C-C)") (class "Default")
      (node (ref "R45") (pin "1") (pinfunction "1_1") (pintype "passive"))
      (node (ref "U22") (pin "12") (pinfunction "C_12") (pintype "passive"))
      (node (ref "U27") (pin "1") (pinfunction "G_1") (pintype "passive"))
    )
    (net (code "42") (name "Net-(U22D-A)") (class "Default")
      (node (ref "R40") (pin "2") (pinfunction "2_2") (pintype "passive"))
      (node (ref "U22") (pin "7") (pinfunction "A_7") (pintype "passive"))
    )
    (net (code "43") (name "Net-(U22D-C)") (class "Default")
      (node (ref "R46") (pin "1") (pinfunction "1_1") (pintype "passive"))
      (node (ref "U22") (pin "10") (pinfunction "C_10") (pintype "passive"))
      (node (ref "U28") (pin "1") (pinfunction "G_1") (pintype "passive"))
    )
    (net (code "44") (name "Net-(U29A-A)") (class "Default")
      (node (ref "R47") (pin "2") (pinfunction "2_2") (pintype "passive"))
      (node (ref "U29") (pin "1") (pinfunction "A_1") (pintype "passive"))
    )
    (net (code "45") (name "Net-(U29A-C)") (class "Default")
      (node (ref "R51") (pin "1") (pinfunction "1_1") (pintype "passive"))
      (node (ref "U29") (pin "16") (pinfunction "C_16") (pintype "passive"))
      (node (ref "U30") (pin "1") (pinfunction "G_1") (pintype "passive"))
    )
    (net (code "46") (name "Net-(U29B-A)") (class "Default")
      (node (ref "R48") (pin "2") (pinfunction "2_2") (pintype "passive"))
      (node (ref "U29") (pin "3") (pinfunction "A_3") (pintype "passive"))
    )
    (net (code "47") (name "Net-(U29B-C)") (class "Default")
      (node (ref "R52") (pin "1") (pinfunction "1_1") (pintype "passive"))
      (node (ref "U29") (pin "14") (pinfunction "C_14") (pintype "passive"))
      (node (ref "U31") (pin "1") (pinfunction "G_1") (pintype "passive"))
    )
    (net (code "48") (name "Net-(U29C-A)") (class "Default")
      (node (ref "R49") (pin "2") (pinfunction "2_2") (pintype "passive"))
      (node (ref "U29") (pin "5") (pinfunction "A_5") (pintype "passive"))
    )
    (net (code "49") (name "Net-(U29C-C)") (class "Default")
      (node (ref "R53") (pin "1") (pinfunction "1_1") (pintype "passive"))
      (node (ref "U29") (pin "12") (pinfunction "C_12") (pintype "passive"))
      (node (ref "U32") (pin "1") (pinfunction "G_1") (pintype "passive"))
    )
    (net (code "50") (name "Net-(U29D-A)") (class "Default")
      (node (ref "R50") (pin "2") (pinfunction "2_2") (pintype "passive"))
      (node (ref "U29") (pin "7") (pinfunction "A_7") (pintype "passive"))
    )
    (net (code "51") (name "Net-(U29D-C)") (class "Default")
      (node (ref "R54") (pin "1") (pinfunction "1_1") (pintype "passive"))
      (node (ref "U29") (pin "10") (pinfunction "C_10") (pintype "passive"))
      (node (ref "U33") (pin "1") (pinfunction "G_1") (pintype "passive"))
    )
    (net (code "52") (name "in_lock1") (class "Default")
      (node (ref "R23") (pin "1") (pinfunction "1_1") (pintype "passive"))
    )
    (net (code "53") (name "in_lock2") (class "Default")
      (node (ref "R24") (pin "1") (pinfunction "1_1") (pintype "passive"))
    )
    (net (code "54") (name "in_lock3") (class "Default")
      (node (ref "R25") (pin "1") (pinfunction "1_1") (pintype "passive"))
    )
    (net (code "55") (name "in_lock4") (class "Default")
      (node (ref "R26") (pin "1") (pinfunction "1_1") (pintype "passive"))
    )
    (net (code "56") (name "in_lock5") (class "Default")
      (node (ref "R27") (pin "1") (pinfunction "1_1") (pintype "passive"))
    )
    (net (code "57") (name "in_lock6") (class "Default")
      (node (ref "R28") (pin "1") (pinfunction "1_1") (pintype "passive"))
    )
    (net (code "58") (name "in_lock7") (class "Default")
      (node (ref "R35") (pin "1") (pinfunction "1_1") (pintype "passive"))
    )
    (net (code "59") (name "in_lock8") (class "Default")
      (node (ref "R36") (pin "1") (pinfunction "1_1") (pintype "passive"))
    )
    (net (code "60") (name "in_lock9") (class "Default")
      (node (ref "R37") (pin "1") (pinfunction "1_1") (pintype "passive"))
    )
    (net (code "61") (name "in_lock10") (class "Default")
      (node (ref "R38") (pin "1") (pinfunction "1_1") (pintype "passive"))
    )
    (net (code "62") (name "in_lock11") (class "Default")
      (node (ref "R39") (pin "1") (pinfunction "1_1") (pintype "passive"))
    )
    (net (code "63") (name "in_lock12") (class "Default")
      (node (ref "R40") (pin "1") (pinfunction "1_1") (pintype "passive"))
    )
    (net (code "64") (name "in_lock13") (class "Default")
      (node (ref "R47") (pin "1") (pinfunction "1_1") (pintype "passive"))
    )
    (net (code "65") (name "in_lock14") (class "Default")
      (node (ref "R48") (pin "1") (pinfunction "1_1") (pintype "passive"))
    )
    (net (code "66") (name "in_lock15") (class "Default")
      (node (ref "R49") (pin "1") (pinfunction "1_1") (pintype "passive"))
    )
    (net (code "67") (name "in_lock16") (class "Default")
      (node (ref "R50") (pin "1") (pinfunction "1_1") (pintype "passive"))
    )
  )
)
